# MCU.net
KiCad netlist of a schematic drawn in Altium Designer
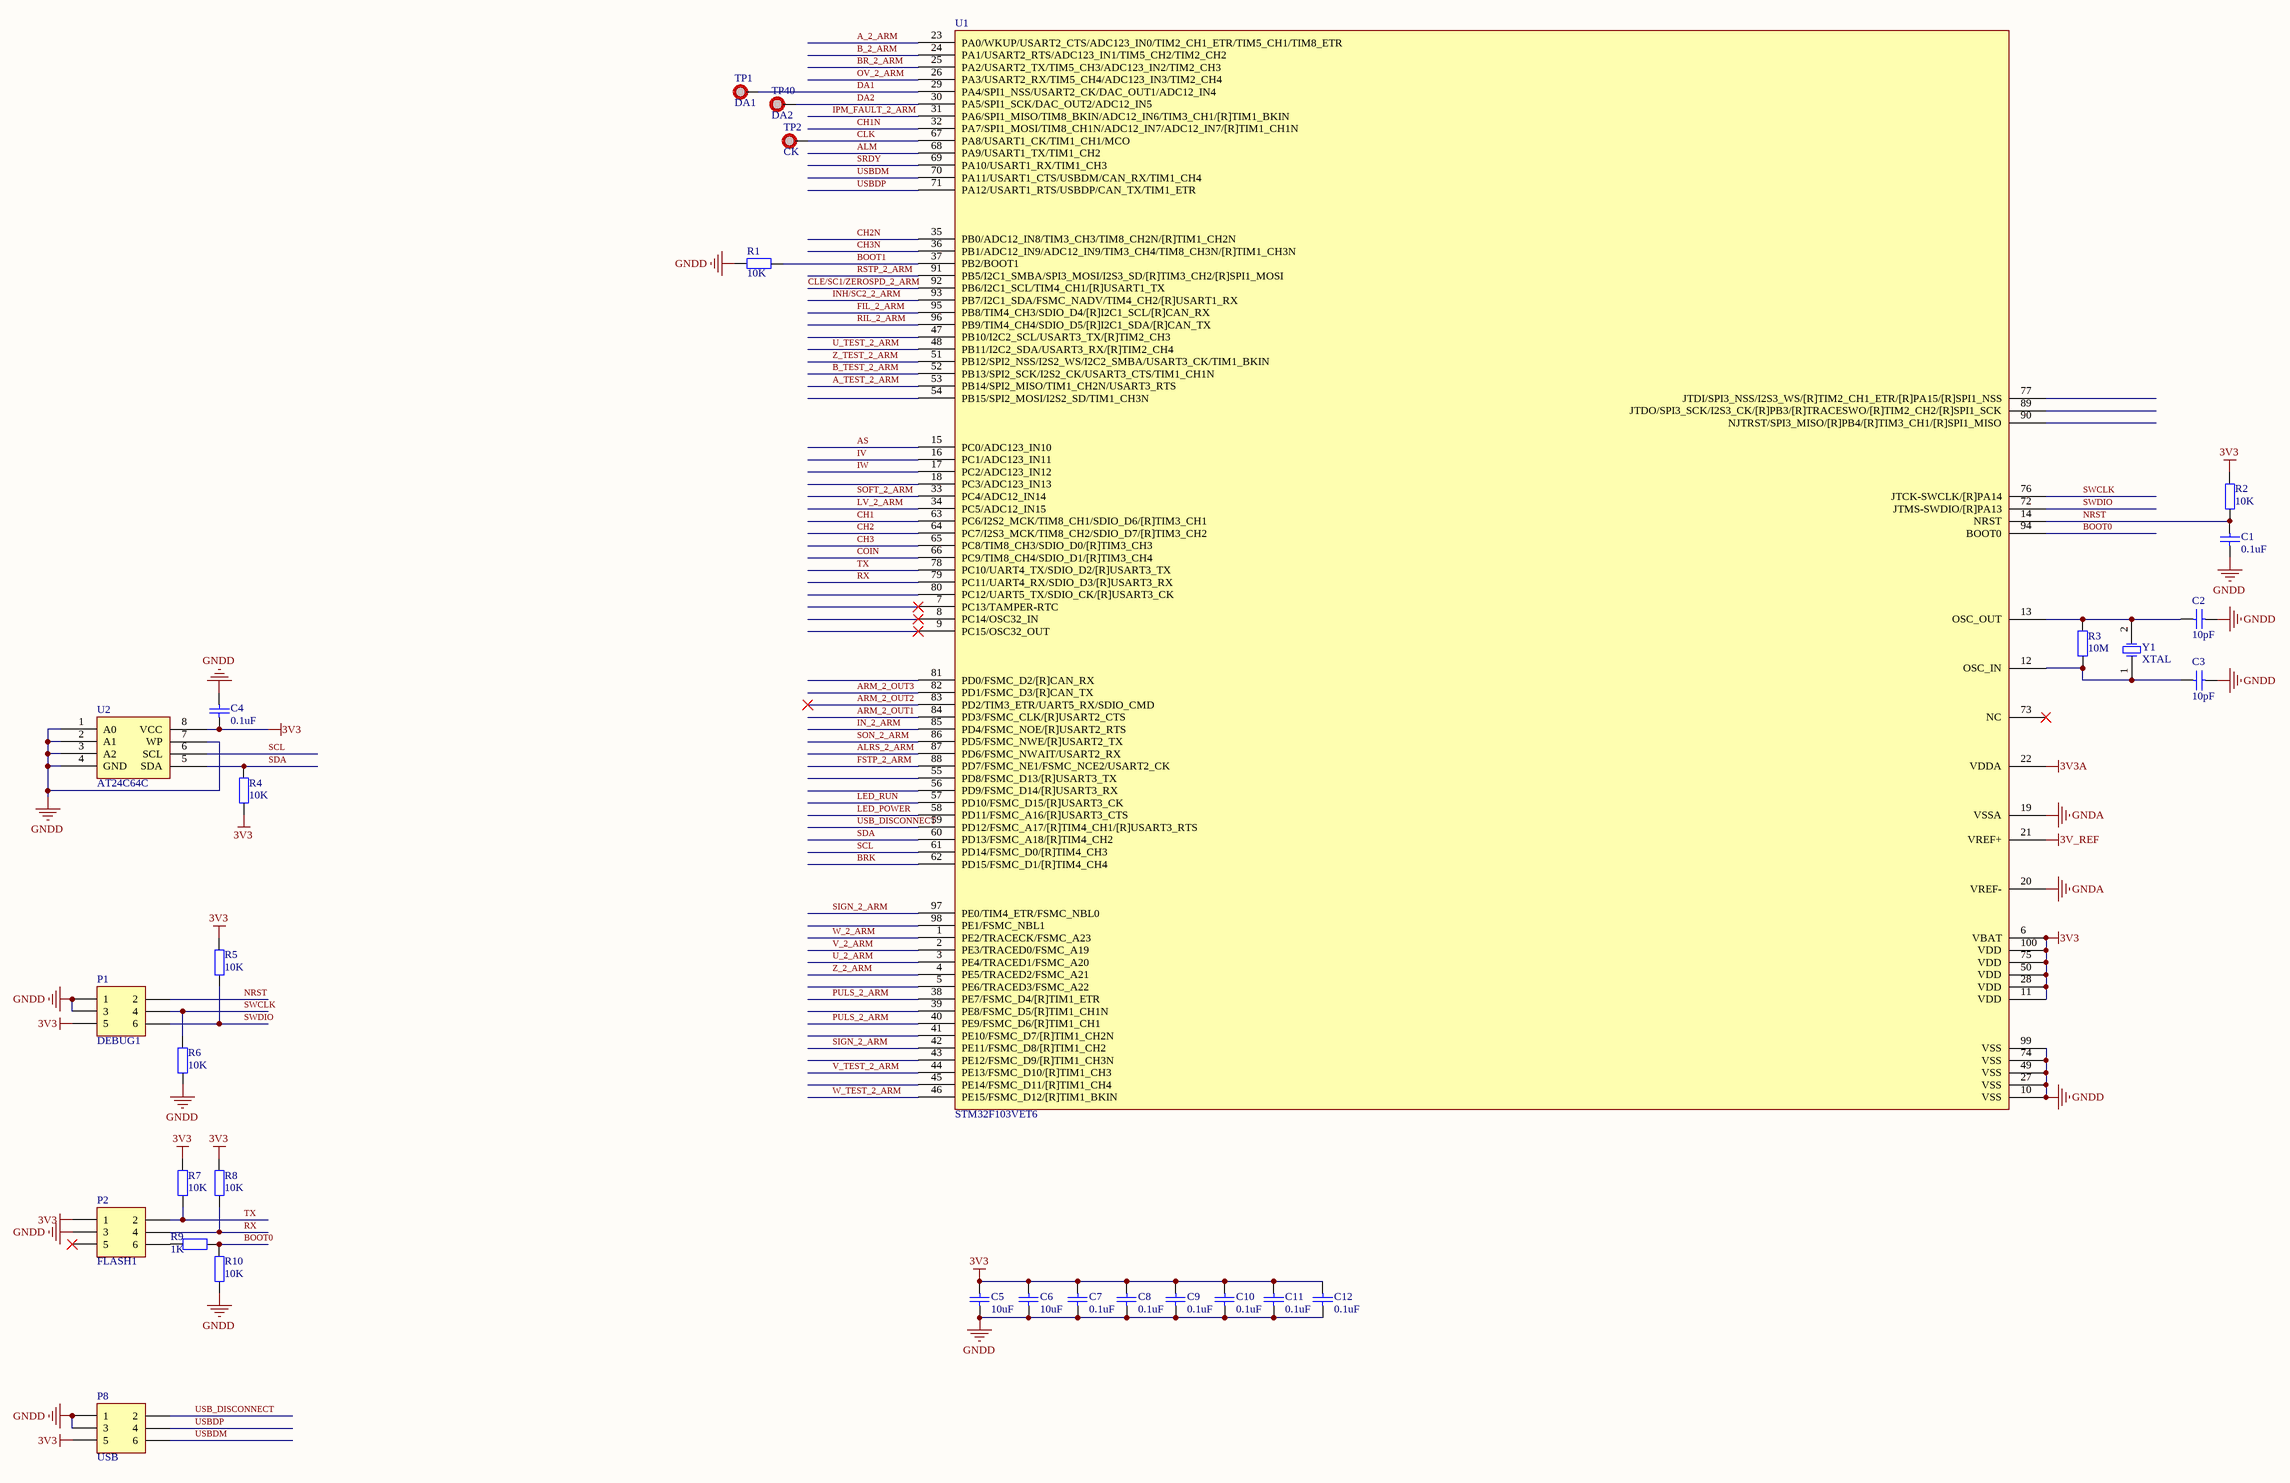
[diagram p0: MCU.SchDoc]

(export (version "E")
  (design (tool "Eeschema 10.0.6"))
  (components
    (comp (ref "C1")
      (value "0.1uF")
      (footprint "C SMD 0603")
      (description "Capacitor")
      (fields (field (name "PUBLISHER") "Altium Limited"))
      (libsource (lib "Miscellaneous Devices") (part "Cap"))
    )
    (comp (ref "C2")
      (value "10pF")
      (footprint "C SMD 0603")
      (description "Capacitor")
      (fields (field (name "PUBLISHER") "Altium Limited"))
      (libsource (lib "Miscellaneous Devices") (part "Cap"))
    )
    (comp (ref "C3")
      (value "10pF")
      (footprint "C SMD 0603")
      (description "Capacitor")
      (fields (field (name "PUBLISHER") "Altium Limited"))
      (libsource (lib "Miscellaneous Devices") (part "Cap"))
    )
    (comp (ref "C4")
      (value "0.1uF")
      (footprint "C SMD 0603")
      (description "Capacitor")
      (fields (field (name "PUBLISHER") "Altium Limited"))
      (libsource (lib "Miscellaneous Devices") (part "Cap"))
    )
    (comp (ref "C5")
      (value "10uF")
      (footprint "C SMD 1206")
      (description "Capacitor")
      (fields (field (name "PUBLISHER") "Altium Limited"))
      (libsource (lib "Miscellaneous Devices") (part "Cap"))
    )
    (comp (ref "C6")
      (value "10uF")
      (footprint "C SMD 1206")
      (description "Capacitor")
      (fields (field (name "PUBLISHER") "Altium Limited"))
      (libsource (lib "Miscellaneous Devices") (part "Cap"))
    )
    (comp (ref "C7")
      (value "0.1uF")
      (footprint "C SMD 0603")
      (description "Capacitor")
      (fields (field (name "PUBLISHER") "Altium Limited"))
      (libsource (lib "Miscellaneous Devices") (part "Cap"))
    )
    (comp (ref "C8")
      (value "0.1uF")
      (footprint "C SMD 0603")
      (description "Capacitor")
      (fields (field (name "PUBLISHER") "Altium Limited"))
      (libsource (lib "Miscellaneous Devices") (part "Cap"))
    )
    (comp (ref "C9")
      (value "0.1uF")
      (footprint "C SMD 0603")
      (description "Capacitor")
      (fields (field (name "PUBLISHER") "Altium Limited"))
      (libsource (lib "Miscellaneous Devices") (part "Cap"))
    )
    (comp (ref "C10")
      (value "0.1uF")
      (footprint "C SMD 0603")
      (description "Capacitor")
      (fields (field (name "PUBLISHER") "Altium Limited"))
      (libsource (lib "Miscellaneous Devices") (part "Cap"))
    )
    (comp (ref "C11")
      (value "0.1uF")
      (footprint "C SMD 0603")
      (description "Capacitor")
      (fields (field (name "PUBLISHER") "Altium Limited"))
      (libsource (lib "Miscellaneous Devices") (part "Cap"))
    )
    (comp (ref "C12")
      (value "0.1uF")
      (footprint "C SMD 0603")
      (description "Capacitor")
      (fields (field (name "PUBLISHER") "Altium Limited"))
      (libsource (lib "Miscellaneous Devices") (part "Cap"))
    )
    (comp (ref "P1")
      (value "DEBUG1")
      (footprint "2.54 针 3*2")
      (description "Header, 3-Pin, Dual row")
      (fields (field (name "PUBLISHER") "Altium Limited"))
      (libsource (lib "Miscellaneous Connectors") (part "Header 3X2"))
    )
    (comp (ref "P2")
      (value "FLASH1")
      (footprint "2.54 针 3*2")
      (description "Header, 3-Pin, Dual row")
      (fields (field (name "PUBLISHER") "Altium Limited"))
      (libsource (lib "Miscellaneous Connectors") (part "Header 3X2"))
    )
    (comp (ref "P8")
      (value "USB")
      (footprint "2.54 针 3*2")
      (description "Header, 3-Pin, Dual row")
      (fields (field (name "PUBLISHER") "Altium Limited"))
      (libsource (lib "Miscellaneous Connectors") (part "Header 3X2"))
    )
    (comp (ref "R1")
      (value "10K")
      (footprint "R SMD 0603")
      (description "Resistor")
      (fields (field (name "PUBLISHER") "Altium Limited"))
      (libsource (lib "") (part "Res2_1"))
    )
    (comp (ref "R2")
      (value "10K")
      (footprint "R SMD 0603")
      (description "Resistor")
      (fields (field (name "PUBLISHER") "Altium Limited"))
      (libsource (lib "Miscellaneous Devices") (part "Res2"))
    )
    (comp (ref "R3")
      (value "10M")
      (footprint "R SMD 0603")
      (description "Resistor")
      (fields (field (name "PUBLISHER") "Altium Limited"))
      (libsource (lib "") (part "Res2_2"))
    )
    (comp (ref "R4")
      (value "10K")
      (footprint "R SMD 0603")
      (description "Resistor")
      (fields (field (name "PUBLISHER") "Altium Limited"))
      (libsource (lib "") (part "Res2_2"))
    )
    (comp (ref "R5")
      (value "10K")
      (footprint "R SMD 0603")
      (description "Resistor")
      (fields (field (name "PUBLISHER") "Altium Limited"))
      (libsource (lib "Miscellaneous Devices") (part "Res2"))
    )
    (comp (ref "R6")
      (value "10K")
      (footprint "R SMD 0603")
      (description "Resistor")
      (fields (field (name "PUBLISHER") "Altium Limited"))
      (libsource (lib "Miscellaneous Devices") (part "Res2"))
    )
    (comp (ref "R7")
      (value "10K")
      (footprint "R SMD 0603")
      (description "Resistor")
      (fields (field (name "PUBLISHER") "Altium Limited"))
      (libsource (lib "Miscellaneous Devices") (part "Res2"))
    )
    (comp (ref "R8")
      (value "10K")
      (footprint "R SMD 0603")
      (description "Resistor")
      (fields (field (name "PUBLISHER") "Altium Limited"))
      (libsource (lib "Miscellaneous Devices") (part "Res2"))
    )
    (comp (ref "R9")
      (value "1K")
      (footprint "R SMD 0603")
      (description "Resistor")
      (fields (field (name "PUBLISHER") "Altium Limited"))
      (libsource (lib "") (part "Res2_1"))
    )
    (comp (ref "R10")
      (value "10K")
      (footprint "R SMD 0603")
      (description "Resistor")
      (fields (field (name "PUBLISHER") "Altium Limited"))
      (libsource (lib "") (part "Res2_2"))
    )
    (comp (ref "TP1") (value "DA1") (libsource (lib "mysch") (part "TEST_POINT")))
    (comp (ref "TP2") (value "CK") (libsource (lib "mysch") (part "TEST_POINT")))
    (comp (ref "TP40") (value "DA2") (libsource (lib "mysch") (part "TEST_POINT")))
    (comp (ref "U1")
      (value "STM32F103VET6")
      (footprint "LQFP100_L")
      (libsource (lib "mysch") (part "STM32F103VET6"))
    )
    (comp (ref "U2") (value "AT24C64C") (footprint "TSSOP8") (libsource (lib "mysch") (part "AT24C64C")))
    (comp (ref "Y1")
      (value "XTAL")
      (footprint "XTAL")
      (description "Crystal Oscillator")
      (fields (field (name "PUBLISHER") "Altium Limited"))
      (libsource (lib "Miscellaneous Devices") (part "XTAL"))
    )
  )
  (nets
    (net (code "1") (name "/ALM") (class "Default")
      (node (ref "U1") (pin "68") (pinfunction "PA9/USART1_TX/TIM1_CH2_68") (pintype "passive"))
    )
    (net (code "2") (name "/ALRS_2_ARM") (class "Default")
      (node (ref "U1") (pin "87") (pinfunction "PD6/FSMC_NWAIT/USART2_RX_87") (pintype "passive"))
    )
    (net (code "3") (name "/ARM_2_OUT1") (class "Default")
      (node (ref "U1") (pin "84") (pinfunction "PD3/FSMC_CLK/[R]USART2_CTS_84") (pintype "passive"))
    )
    (net (code "4") (name "/ARM_2_OUT2") (class "Default")
      (node (ref "U1") (pin "83") (pinfunction "PD2/TIM3_ETR/UART5_RX/SDIO_CMD_83") (pintype "passive+no_connect"))
    )
    (net (code "5") (name "/ARM_2_OUT3") (class "Default")
      (node (ref "U1") (pin "82") (pinfunction "PD1/FSMC_D3/[R]CAN_TX_82") (pintype "passive"))
    )
    (net (code "6") (name "/AS") (class "Default")
      (node (ref "U1") (pin "15") (pinfunction "PC0/ADC123_IN10_15") (pintype "passive"))
    )
    (net (code "7") (name "/A_2_ARM") (class "Default")
      (node (ref "U1") (pin "23") (pinfunction "PA0/WKUP/USART2_CTS/ADC123_IN0/TIM2_CH1_ETR/TIM5_CH1/TIM8_ETR_23") (pintype "passive"))
    )
    (net (code "8") (name "/A_TEST_2_ARM") (class "Default")
      (node (ref "U1") (pin "53") (pinfunction "PB14/SPI2_MISO/TIM1_CH2N/USART3_RTS_53") (pintype "passive"))
    )
    (net (code "9") (name "/BOOT0") (class "Default")
      (node (ref "R10") (pin "1") (pinfunction "1_1") (pintype "passive"))
      (node (ref "R9") (pin "1") (pinfunction "1_1") (pintype "passive"))
      (node (ref "U1") (pin "94") (pinfunction "BOOT0_94") (pintype "passive"))
    )
    (net (code "10") (name "/BOOT1") (class "Default")
      (node (ref "R1") (pin "1") (pinfunction "1_1") (pintype "passive"))
      (node (ref "U1") (pin "37") (pinfunction "PB2/BOOT1_37") (pintype "passive"))
    )
    (net (code "11") (name "/BRK") (class "Default")
      (node (ref "U1") (pin "62") (pinfunction "PD15/FSMC_D1/[R]TIM4_CH4_62") (pintype "passive"))
    )
    (net (code "12") (name "/BR_2_ARM") (class "Default")
      (node (ref "U1") (pin "25") (pinfunction "PA2/USART2_TX/TIM5_CH3/ADC123_IN2/TIM2_CH3_25") (pintype "passive"))
    )
    (net (code "13") (name "/B_2_ARM") (class "Default")
      (node (ref "U1") (pin "24") (pinfunction "PA1/USART2_RTS/ADC123_IN1/TIM5_CH2/TIM2_CH2_24") (pintype "passive"))
    )
    (net (code "14") (name "/B_TEST_2_ARM") (class "Default")
      (node (ref "U1") (pin "52") (pinfunction "PB13/SPI2_SCK/I2S2_CK/USART3_CTS/TIM1_CH1N_52") (pintype "passive"))
    )
    (net (code "15") (name "/CH1") (class "Default")
      (node (ref "U1") (pin "63") (pinfunction "PC6/I2S2_MCK/TIM8_CH1/SDIO_D6/[R]TIM3_CH1_63") (pintype "passive"))
    )
    (net (code "16") (name "/CH1N") (class "Default")
      (node (ref "U1") (pin "32") (pinfunction "PA7/SPI1_MOSI/TIM8_CH1N/ADC12_IN7/ADC12_IN7/[R]TIM1_CH1N_32") (pintype "passive"))
    )
    (net (code "17") (name "/CH2") (class "Default")
      (node (ref "U1") (pin "64") (pinfunction "PC7/I2S3_MCK/TIM8_CH2/SDIO_D7/[R]TIM3_CH2_64") (pintype "passive"))
    )
    (net (code "18") (name "/CH2N") (class "Default")
      (node (ref "U1") (pin "35") (pinfunction "PB0/ADC12_IN8/TIM3_CH3/TIM8_CH2N/[R]TIM1_CH2N_35") (pintype "passive"))
    )
    (net (code "19") (name "/CH3") (class "Default")
      (node (ref "U1") (pin "65") (pinfunction "PC8/TIM8_CH3/SDIO_D0/[R]TIM3_CH3_65") (pintype "passive"))
    )
    (net (code "20") (name "/CH3N") (class "Default")
      (node (ref "U1") (pin "36") (pinfunction "PB1/ADC12_IN9/ADC12_IN9/TIM3_CH4/TIM8_CH3N/[R]TIM1_CH3N_36") (pintype "passive"))
    )
    (net (code "21") (name "/CLE{slash}SC1{slash}ZEROSPD_2_ARM") (class "Default")
      (node (ref "U1") (pin "92") (pinfunction "PB6/I2C1_SCL/TIM4_CH1/[R]USART1_TX_92") (pintype "passive"))
    )
    (net (code "22") (name "/CLK") (class "Default")
      (node (ref "TP2") (pin "1") (pinfunction "1_1") (pintype "passive"))
      (node (ref "U1") (pin "67") (pinfunction "PA8/USART1_CK/TIM1_CH1/MCO_67") (pintype "passive"))
    )
    (net (code "23") (name "/COIN") (class "Default")
      (node (ref "U1") (pin "66") (pinfunction "PC9/TIM8_CH4/SDIO_D1/[R]TIM3_CH4_66") (pintype "passive"))
    )
    (net (code "24") (name "/DA1") (class "Default")
      (node (ref "TP1") (pin "1") (pinfunction "1_1") (pintype "passive"))
      (node (ref "U1") (pin "29") (pinfunction "PA4/SPI1_NSS/USART2_CK/DAC_OUT1/ADC12_IN4_29") (pintype "passive"))
    )
    (net (code "25") (name "/DA2") (class "Default")
      (node (ref "TP40") (pin "1") (pinfunction "1_1") (pintype "passive"))
      (node (ref "U1") (pin "30") (pinfunction "PA5/SPI1_SCK/DAC_OUT2/ADC12_IN5_30") (pintype "passive"))
    )
    (net (code "26") (name "/FIL_2_ARM") (class "Default")
      (node (ref "U1") (pin "95") (pinfunction "PB8/TIM4_CH3/SDIO_D4/[R]I2C1_SCL/[R]CAN_RX_95") (pintype "passive"))
    )
    (net (code "27") (name "/FSTP_2_ARM") (class "Default")
      (node (ref "U1") (pin "88") (pinfunction "PD7/FSMC_NE1/FSMC_NCE2/USART2_CK_88") (pintype "passive"))
    )
    (net (code "28") (name "/INH{slash}SC2_2_ARM") (class "Default")
      (node (ref "U1") (pin "93") (pinfunction "PB7/I2C1_SDA/FSMC_NADV/TIM4_CH2/[R]USART1_RX_93") (pintype "passive"))
    )
    (net (code "29") (name "/IN_2_ARM") (class "Default")
      (node (ref "U1") (pin "85") (pinfunction "PD4/FSMC_NOE/[R]USART2_RTS_85") (pintype "passive"))
    )
    (net (code "30") (name "/IPM_FAULT_2_ARM") (class "Default")
      (node (ref "U1") (pin "31") (pinfunction "PA6/SPI1_MISO/TIM8_BKIN/ADC12_IN6/TIM3_CH1/[R]TIM1_BKIN_31") (pintype "passive"))
    )
    (net (code "31") (name "/IV") (class "Default")
      (node (ref "U1") (pin "16") (pinfunction "PC1/ADC123_IN11_16") (pintype "passive"))
    )
    (net (code "32") (name "/IW") (class "Default")
      (node (ref "U1") (pin "17") (pinfunction "PC2/ADC123_IN12_17") (pintype "passive"))
    )
    (net (code "33") (name "/LED_POWER") (class "Default")
      (node (ref "U1") (pin "58") (pinfunction "PD11/FSMC_A16/[R]USART3_CTS_58") (pintype "passive"))
    )
    (net (code "34") (name "/LED_RUN") (class "Default")
      (node (ref "U1") (pin "57") (pinfunction "PD10/FSMC_D15/[R]USART3_CK_57") (pintype "passive"))
    )
    (net (code "35") (name "/LV_2_ARM") (class "Default")
      (node (ref "U1") (pin "34") (pinfunction "PC5/ADC12_IN15_34") (pintype "passive"))
    )
    (net (code "36") (name "/NRST") (class "Default")
      (node (ref "C1") (pin "1") (pinfunction "1_1") (pintype "passive"))
      (node (ref "P1") (pin "2") (pinfunction "2_2") (pintype "passive"))
      (node (ref "R2") (pin "1") (pinfunction "1_1") (pintype "passive"))
      (node (ref "U1") (pin "14") (pinfunction "NRST_14") (pintype "passive"))
    )
    (net (code "37") (name "/OV_2_ARM") (class "Default")
      (node (ref "U1") (pin "26") (pinfunction "PA3/USART2_RX/TIM5_CH4/ADC123_IN3/TIM2_CH4_26") (pintype "passive"))
    )
    (net (code "38") (name "/PULS_2_ARM") (class "Default")
      (node (ref "U1") (pin "38") (pinfunction "PE7/FSMC_D4/[R]TIM1_ETR_38") (pintype "passive"))
      (node (ref "U1") (pin "40") (pinfunction "PE9/FSMC_D6/[R]TIM1_CH1_40") (pintype "passive"))
    )
    (net (code "39") (name "/RIL_2_ARM") (class "Default")
      (node (ref "U1") (pin "96") (pinfunction "PB9/TIM4_CH4/SDIO_D5/[R]I2C1_SDA/[R]CAN_TX_96") (pintype "passive"))
    )
    (net (code "40") (name "/RSTP_2_ARM") (class "Default")
      (node (ref "U1") (pin "91") (pinfunction "PB5/I2C1_SMBA/SPI3_MOSI/I2S3_SD/[R]TIM3_CH2/[R]SPI1_MOSI_91") (pintype "passive"))
    )
    (net (code "41") (name "/RX") (class "Default")
      (node (ref "P2") (pin "4") (pinfunction "4_4") (pintype "passive"))
      (node (ref "R8") (pin "1") (pinfunction "1_1") (pintype "passive"))
      (node (ref "U1") (pin "79") (pinfunction "PC11/UART4_RX/SDIO_D3/[R]USART3_RX_79") (pintype "passive"))
    )
    (net (code "42") (name "/SCL") (class "Default")
      (node (ref "U1") (pin "61") (pinfunction "PD14/FSMC_D0/[R]TIM4_CH3_61") (pintype "passive"))
      (node (ref "U2") (pin "6") (pinfunction "SCL_6") (pintype "passive"))
    )
    (net (code "43") (name "/SDA") (class "Default")
      (node (ref "R4") (pin "1") (pinfunction "1_1") (pintype "passive"))
      (node (ref "U1") (pin "60") (pinfunction "PD13/FSMC_A18/[R]TIM4_CH2_60") (pintype "passive"))
      (node (ref "U2") (pin "5") (pinfunction "SDA_5") (pintype "passive"))
    )
    (net (code "44") (name "/SIGN_2_ARM") (class "Default")
      (node (ref "U1") (pin "42") (pinfunction "PE11/FSMC_D8/[R]TIM1_CH2_42") (pintype "passive"))
      (node (ref "U1") (pin "97") (pinfunction "PE0/TIM4_ETR/FSMC_NBL0_97") (pintype "passive"))
    )
    (net (code "45") (name "/SOFT_2_ARM") (class "Default")
      (node (ref "U1") (pin "33") (pinfunction "PC4/ADC12_IN14_33") (pintype "passive"))
    )
    (net (code "46") (name "/SON_2_ARM") (class "Default")
      (node (ref "U1") (pin "86") (pinfunction "PD5/FSMC_NWE/[R]USART2_TX_86") (pintype "passive"))
    )
    (net (code "47") (name "/SRDY") (class "Default")
      (node (ref "U1") (pin "69") (pinfunction "PA10/USART1_RX/TIM1_CH3_69") (pintype "passive"))
    )
    (net (code "48") (name "/SWCLK") (class "Default")
      (node (ref "P1") (pin "4") (pinfunction "4_4") (pintype "passive"))
      (node (ref "R6") (pin "2") (pinfunction "2_2") (pintype "passive"))
      (node (ref "U1") (pin "76") (pinfunction "JTCK-SWCLK/[R]PA14_76") (pintype "passive"))
    )
    (net (code "49") (name "/SWDIO") (class "Default")
      (node (ref "P1") (pin "6") (pinfunction "6_6") (pintype "passive"))
      (node (ref "R5") (pin "1") (pinfunction "1_1") (pintype "passive"))
      (node (ref "U1") (pin "72") (pinfunction "JTMS-SWDIO/[R]PA13_72") (pintype "passive"))
    )
    (net (code "50") (name "/TX") (class "Default")
      (node (ref "P2") (pin "2") (pinfunction "2_2") (pintype "passive"))
      (node (ref "R7") (pin "1") (pinfunction "1_1") (pintype "passive"))
      (node (ref "U1") (pin "78") (pinfunction "PC10/UART4_TX/SDIO_D2/[R]USART3_TX_78") (pintype "passive"))
    )
    (net (code "51") (name "/USBDM") (class "Default")
      (node (ref "P8") (pin "6") (pinfunction "6_6") (pintype "passive"))
      (node (ref "U1") (pin "70") (pinfunction "PA11/USART1_CTS/USBDM/CAN_RX/TIM1_CH4_70") (pintype "passive"))
    )
    (net (code "52") (name "/USBDP") (class "Default")
      (node (ref "P8") (pin "4") (pinfunction "4_4") (pintype "passive"))
      (node (ref "U1") (pin "71") (pinfunction "PA12/USART1_RTS/USBDP/CAN_TX/TIM1_ETR_71") (pintype "passive"))
    )
    (net (code "53") (name "/USB_DISCONNECT") (class "Default")
      (node (ref "P8") (pin "2") (pinfunction "2_2") (pintype "passive"))
      (node (ref "U1") (pin "59") (pinfunction "PD12/FSMC_A17/[R]TIM4_CH1/[R]USART3_RTS_59") (pintype "passive"))
    )
    (net (code "54") (name "/U_2_ARM") (class "Default")
      (node (ref "U1") (pin "3") (pinfunction "PE4/TRACED1/FSMC_A20_3") (pintype "passive"))
    )
    (net (code "55") (name "/U_TEST_2_ARM") (class "Default")
      (node (ref "U1") (pin "48") (pinfunction "PB11/I2C2_SDA/USART3_RX/[R]TIM2_CH4_48") (pintype "passive"))
    )
    (net (code "56") (name "/V_2_ARM") (class "Default")
      (node (ref "U1") (pin "2") (pinfunction "PE3/TRACED0/FSMC_A19_2") (pintype "passive"))
    )
    (net (code "57") (name "/V_TEST_2_ARM") (class "Default")
      (node (ref "U1") (pin "44") (pinfunction "PE13/FSMC_D10/[R]TIM1_CH3_44") (pintype "passive"))
    )
    (net (code "58") (name "/W_2_ARM") (class "Default")
      (node (ref "U1") (pin "1") (pinfunction "PE2/TRACECK/FSMC_A23_1") (pintype "passive"))
    )
    (net (code "59") (name "/W_TEST_2_ARM") (class "Default")
      (node (ref "U1") (pin "46") (pinfunction "PE15/FSMC_D12/[R]TIM1_BKIN_46") (pintype "passive"))
    )
    (net (code "60") (name "/Z_2_ARM") (class "Default")
      (node (ref "U1") (pin "4") (pinfunction "PE5/TRACED2/FSMC_A21_4") (pintype "passive"))
    )
    (net (code "61") (name "/Z_TEST_2_ARM") (class "Default")
      (node (ref "U1") (pin "51") (pinfunction "PB12/SPI2_NSS/I2S2_WS/I2C2_SMBA/USART3_CK/TIM1_BKIN_51") (pintype "passive"))
    )
    (net (code "62") (name "3V3") (class "Default")
      (node (ref "C10") (pin "1") (pinfunction "1_1") (pintype "passive"))
      (node (ref "C11") (pin "1") (pinfunction "1_1") (pintype "passive"))
      (node (ref "C12") (pin "1") (pinfunction "1_1") (pintype "passive"))
      (node (ref "C4") (pin "2") (pinfunction "2_2") (pintype "passive"))
      (node (ref "C5") (pin "1") (pinfunction "1_1") (pintype "passive"))
      (node (ref "C6") (pin "1") (pinfunction "1_1") (pintype "passive"))
      (node (ref "C7") (pin "1") (pinfunction "1_1") (pintype "passive"))
      (node (ref "C8") (pin "1") (pinfunction "1_1") (pintype "passive"))
      (node (ref "C9") (pin "1") (pinfunction "1_1") (pintype "passive"))
      (node (ref "P1") (pin "5") (pinfunction "5_5") (pintype "passive"))
      (node (ref "P2") (pin "1") (pinfunction "1_1") (pintype "passive"))
      (node (ref "P8") (pin "5") (pinfunction "5_5") (pintype "passive"))
      (node (ref "R2") (pin "2") (pinfunction "2_2") (pintype "passive"))
      (node (ref "R4") (pin "2") (pinfunction "2_2") (pintype "passive"))
      (node (ref "R5") (pin "2") (pinfunction "2_2") (pintype "passive"))
      (node (ref "R7") (pin "2") (pinfunction "2_2") (pintype "passive"))
      (node (ref "R8") (pin "2") (pinfunction "2_2") (pintype "passive"))
      (node (ref "U1") (pin "100") (pinfunction "VDD_100") (pintype "passive"))
      (node (ref "U1") (pin "11") (pinfunction "VDD_11") (pintype "passive"))
      (node (ref "U1") (pin "28") (pinfunction "VDD_28") (pintype "passive"))
      (node (ref "U1") (pin "50") (pinfunction "VDD_50") (pintype "passive"))
      (node (ref "U1") (pin "6") (pinfunction "VBAT_6") (pintype "passive"))
      (node (ref "U1") (pin "75") (pinfunction "VDD_75") (pintype "passive"))
      (node (ref "U2") (pin "8") (pinfunction "VCC_8") (pintype "passive"))
    )
    (net (code "63") (name "3V3A") (class "Default")
      (node (ref "U1") (pin "22") (pinfunction "VDDA_22") (pintype "passive"))
    )
    (net (code "64") (name "3V_REF") (class "Default")
      (node (ref "U1") (pin "21") (pinfunction "VREF+_21") (pintype "passive"))
    )
    (net (code "65") (name "GNDA") (class "Default")
      (node (ref "U1") (pin "19") (pinfunction "VSSA_19") (pintype "passive"))
      (node (ref "U1") (pin "20") (pinfunction "VREF-_20") (pintype "passive"))
    )
    (net (code "66") (name "GNDD") (class "Default")
      (node (ref "C1") (pin "2") (pinfunction "2_2") (pintype "passive"))
      (node (ref "C10") (pin "2") (pinfunction "2_2") (pintype "passive"))
      (node (ref "C11") (pin "2") (pinfunction "2_2") (pintype "passive"))
      (node (ref "C12") (pin "2") (pinfunction "2_2") (pintype "passive"))
      (node (ref "C2") (pin "2") (pinfunction "2_2") (pintype "passive"))
      (node (ref "C3") (pin "2") (pinfunction "2_2") (pintype "passive"))
      (node (ref "C4") (pin "1") (pinfunction "1_1") (pintype "passive"))
      (node (ref "C5") (pin "2") (pinfunction "2_2") (pintype "passive"))
      (node (ref "C6") (pin "2") (pinfunction "2_2") (pintype "passive"))
      (node (ref "C7") (pin "2") (pinfunction "2_2") (pintype "passive"))
      (node (ref "C8") (pin "2") (pinfunction "2_2") (pintype "passive"))
      (node (ref "C9") (pin "2") (pinfunction "2_2") (pintype "passive"))
      (node (ref "P1") (pin "1") (pinfunction "1_1") (pintype "passive"))
      (node (ref "P1") (pin "3") (pinfunction "3_3") (pintype "passive"))
      (node (ref "P2") (pin "3") (pinfunction "3_3") (pintype "passive"))
      (node (ref "P8") (pin "1") (pinfunction "1_1") (pintype "passive"))
      (node (ref "P8") (pin "3") (pinfunction "3_3") (pintype "passive"))
      (node (ref "R1") (pin "2") (pinfunction "2_2") (pintype "passive"))
      (node (ref "R10") (pin "2") (pinfunction "2_2") (pintype "passive"))
      (node (ref "R6") (pin "1") (pinfunction "1_1") (pintype "passive"))
      (node (ref "U1") (pin "10") (pinfunction "VSS_10") (pintype "passive"))
      (node (ref "U1") (pin "27") (pinfunction "VSS_27") (pintype "passive"))
      (node (ref "U1") (pin "49") (pinfunction "VSS_49") (pintype "passive"))
      (node (ref "U1") (pin "74") (pinfunction "VSS_74") (pintype "passive"))
      (node (ref "U1") (pin "99") (pinfunction "VSS_99") (pintype "passive"))
      (node (ref "U2") (pin "1") (pinfunction "A0_1") (pintype "passive"))
      (node (ref "U2") (pin "2") (pinfunction "A1_2") (pintype "passive"))
      (node (ref "U2") (pin "3") (pinfunction "A2_3") (pintype "passive"))
      (node (ref "U2") (pin "4") (pinfunction "GND_4") (pintype "passive"))
      (node (ref "U2") (pin "7") (pinfunction "WP_7") (pintype "passive"))
    )
    (net (code "67") (name "Net-(P2-Pad6)") (class "Default")
      (node (ref "P2") (pin "6") (pinfunction "6_6") (pintype "passive"))
      (node (ref "R9") (pin "2") (pinfunction "2_2") (pintype "passive"))
    )
    (net (code "68") (name "Net-(U1-OSC_IN)") (class "Default")
      (node (ref "C3") (pin "1") (pinfunction "1_1") (pintype "passive"))
      (node (ref "R3") (pin "2") (pinfunction "2_2") (pintype "passive"))
      (node (ref "U1") (pin "12") (pinfunction "OSC_IN_12") (pintype "passive"))
      (node (ref "Y1") (pin "1") (pinfunction "OSC1_1") (pintype "passive"))
    )
    (net (code "69") (name "Net-(U1-OSC_OUT)") (class "Default")
      (node (ref "C2") (pin "1") (pinfunction "1_1") (pintype "passive"))
      (node (ref "R3") (pin "1") (pinfunction "1_1") (pintype "passive"))
      (node (ref "U1") (pin "13") (pinfunction "OSC_OUT_13") (pintype "passive"))
      (node (ref "Y1") (pin "2") (pinfunction "OSC2_2") (pintype "passive"))
    )
    (net (code "70") (name "unconnected-(P2-Pad5)") (class "Default")
      (node (ref "P2") (pin "5") (pinfunction "5_5") (pintype "passive+no_connect"))
    )
    (net (code "71") (name "unconnected-(U1-JTDI{slash}SPI3_NSS{slash}I2S3_WS{slash}[R]TIM2_CH1_ETR{slash}[R]PA15{slash}[R]SPI1_NSS-Pad77)") (class "Default")
      (node (ref "U1") (pin "77") (pinfunction "JTDI/SPI3_NSS/I2S3_WS/[R]TIM2_CH1_ETR/[R]PA15/[R]SPI1_NSS_77") (pintype "passive"))
    )
    (net (code "72") (name "unconnected-(U1-JTDO{slash}SPI3_SCK{slash}I2S3_CK{slash}[R]PB3{slash}[R]TRACESWO{slash}[R]TIM2_CH2{slash}[R]SPI1_SCK-Pad89)") (class "Default")
      (node (ref "U1") (pin "89") (pinfunction "JTDO/SPI3_SCK/I2S3_CK/[R]PB3/[R]TRACESWO/[R]TIM2_CH2/[R]SPI1_SCK_89") (pintype "passive"))
    )
    (net (code "73") (name "unconnected-(U1-NC-Pad73)") (class "Default")
      (node (ref "U1") (pin "73") (pinfunction "NC_73") (pintype "passive+no_connect"))
    )
    (net (code "74") (name "unconnected-(U1-NJTRST{slash}SPI3_MISO{slash}[R]PB4{slash}[R]TIM3_CH1{slash}[R]SPI1_MISO-Pad90)") (class "Default")
      (node (ref "U1") (pin "90") (pinfunction "NJTRST/SPI3_MISO/[R]PB4/[R]TIM3_CH1/[R]SPI1_MISO_90") (pintype "passive"))
    )
    (net (code "75") (name "unconnected-(U1-PB10{slash}I2C2_SCL{slash}USART3_TX{slash}[R]TIM2_CH3-Pad47)") (class "Default")
      (node (ref "U1") (pin "47") (pinfunction "PB10/I2C2_SCL/USART3_TX/[R]TIM2_CH3_47") (pintype "passive"))
    )
    (net (code "76") (name "unconnected-(U1-PB15{slash}SPI2_MOSI{slash}I2S2_SD{slash}TIM1_CH3N-Pad54)") (class "Default")
      (node (ref "U1") (pin "54") (pinfunction "PB15/SPI2_MOSI/I2S2_SD/TIM1_CH3N_54") (pintype "passive"))
    )
    (net (code "77") (name "unconnected-(U1-PC3{slash}ADC123_IN13-Pad18)") (class "Default")
      (node (ref "U1") (pin "18") (pinfunction "PC3/ADC123_IN13_18") (pintype "passive"))
    )
    (net (code "78") (name "unconnected-(U1-PC12{slash}UART5_TX{slash}SDIO_CK{slash}[R]USART3_CK-Pad80)") (class "Default")
      (node (ref "U1") (pin "80") (pinfunction "PC12/UART5_TX/SDIO_CK/[R]USART3_CK_80") (pintype "passive"))
    )
    (net (code "79") (name "unconnected-(U1-PC13{slash}TAMPER-RTC-Pad7)") (class "Default")
      (node (ref "U1") (pin "7") (pinfunction "PC13/TAMPER-RTC_7") (pintype "passive+no_connect"))
    )
    (net (code "80") (name "unconnected-(U1-PC14{slash}OSC32_IN-Pad8)") (class "Default")
      (node (ref "U1") (pin "8") (pinfunction "PC14/OSC32_IN_8") (pintype "passive+no_connect"))
    )
    (net (code "81") (name "unconnected-(U1-PC15{slash}OSC32_OUT-Pad9)") (class "Default")
      (node (ref "U1") (pin "9") (pinfunction "PC15/OSC32_OUT_9") (pintype "passive+no_connect"))
    )
    (net (code "82") (name "unconnected-(U1-PD0{slash}FSMC_D2{slash}[R]CAN_RX-Pad81)") (class "Default")
      (node (ref "U1") (pin "81") (pinfunction "PD0/FSMC_D2/[R]CAN_RX_81") (pintype "passive"))
    )
    (net (code "83") (name "unconnected-(U1-PD8{slash}FSMC_D13{slash}[R]USART3_TX-Pad55)") (class "Default")
      (node (ref "U1") (pin "55") (pinfunction "PD8/FSMC_D13/[R]USART3_TX_55") (pintype "passive"))
    )
    (net (code "84") (name "unconnected-(U1-PD9{slash}FSMC_D14{slash}[R]USART3_RX-Pad56)") (class "Default")
      (node (ref "U1") (pin "56") (pinfunction "PD9/FSMC_D14/[R]USART3_RX_56") (pintype "passive"))
    )
    (net (code "85") (name "unconnected-(U1-PE1{slash}FSMC_NBL1-Pad98)") (class "Default")
      (node (ref "U1") (pin "98") (pinfunction "PE1/FSMC_NBL1_98") (pintype "passive"))
    )
    (net (code "86") (name "unconnected-(U1-PE6{slash}TRACED3{slash}FSMC_A22-Pad5)") (class "Default")
      (node (ref "U1") (pin "5") (pinfunction "PE6/TRACED3/FSMC_A22_5") (pintype "passive"))
    )
    (net (code "87") (name "unconnected-(U1-PE8{slash}FSMC_D5{slash}[R]TIM1_CH1N-Pad39)") (class "Default")
      (node (ref "U1") (pin "39") (pinfunction "PE8/FSMC_D5/[R]TIM1_CH1N_39") (pintype "passive"))
    )
    (net (code "88") (name "unconnected-(U1-PE10{slash}FSMC_D7{slash}[R]TIM1_CH2N-Pad41)") (class "Default")
      (node (ref "U1") (pin "41") (pinfunction "PE10/FSMC_D7/[R]TIM1_CH2N_41") (pintype "passive"))
    )
    (net (code "89") (name "unconnected-(U1-PE12{slash}FSMC_D9{slash}[R]TIM1_CH3N-Pad43)") (class "Default")
      (node (ref "U1") (pin "43") (pinfunction "PE12/FSMC_D9/[R]TIM1_CH3N_43") (pintype "passive"))
    )
    (net (code "90") (name "unconnected-(U1-PE14{slash}FSMC_D11{slash}[R]TIM1_CH4-Pad45)") (class "Default")
      (node (ref "U1") (pin "45") (pinfunction "PE14/FSMC_D11/[R]TIM1_CH4_45") (pintype "passive"))
    )
  )
)
